# HandHeld_O2_Analyzer.net
KiCad netlist of a schematic drawn in EAGLE
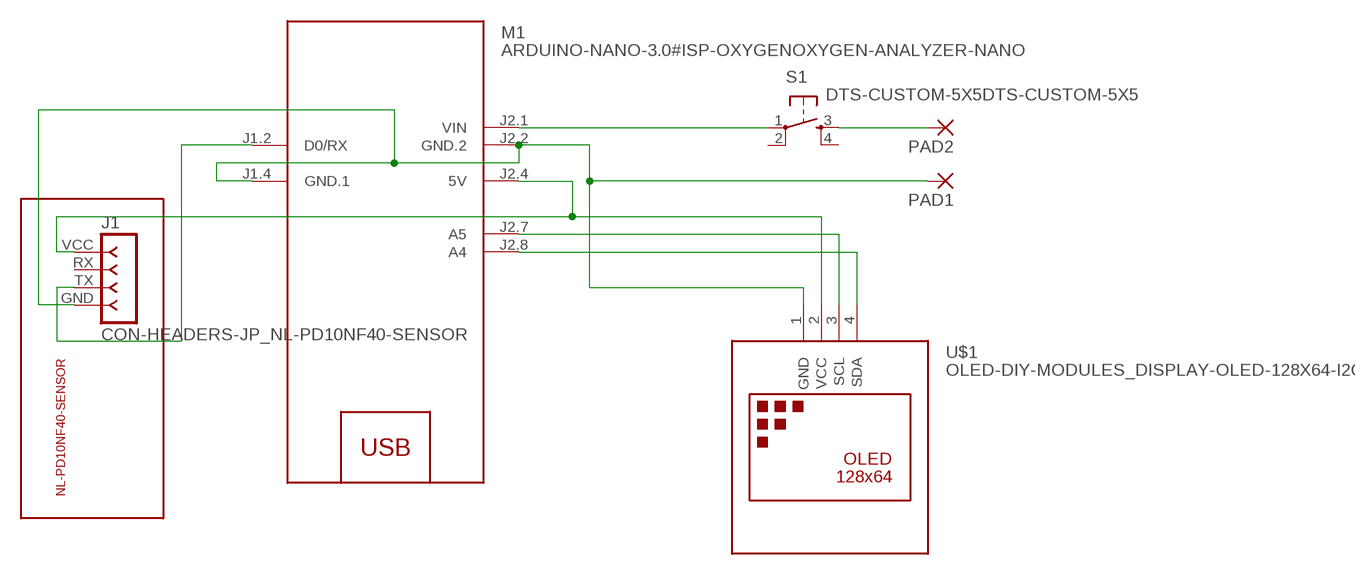
[diagram p0: schematic, sheet 1]

(export (version "E")
  (design (tool "Eeschema 10.0.6"))
  (components
    (comp (ref "J1")
      (value "CON-HEADERS-JP_NL-PD10NF40-SENSOR")
      (footprint "eagle-import:CON-HEADERS-JP_NL-PD10NF40-SENSOR")
      (libsource (lib "eagle-import") (part "CON-HEADERS-JP_NL-PD10NF40-SENSOR"))
    )
    (comp (ref "M1")
      (value "ARDUINO-NANO-3.0#ISP-OXYGENOXYGEN-ANALYZER-NANO")
      (footprint "eagle-import:ARDUINO-NANO-3.0#ISP-OXYGEN")
      (libsource (lib "eagle-import") (part "ARDUINO-NANO-3.0#ISP-OXYGENOXYGEN-ANALYZER-NANO"))
    )
    (comp (ref "PAD1")
      (value "WIREPAD_2,54/0,8")
      (footprint "eagle-import:WIREPAD_2,54_0,8")
      (libsource (lib "eagle-import") (part "WIREPAD_2,54/0,8"))
    )
    (comp (ref "PAD2")
      (value "WIREPAD_2,54/0,8")
      (footprint "eagle-import:WIREPAD_2,54_0,8")
      (libsource (lib "eagle-import") (part "WIREPAD_2,54/0,8"))
    )
    (comp (ref "S1")
      (value "DTS-CUSTOM-5X5DTS-CUSTOM-5X5")
      (footprint "eagle-import:DTS-CUSTOM-5X5")
      (libsource (lib "eagle-import") (part "DTS-CUSTOM-5X5DTS-CUSTOM-5X5"))
    )
    (comp (ref "U$1")
      (value "OLED-DIY-MODULES_DISPLAY-OLED-128X64-I2C")
      (footprint "eagle-import:OLED-DIY-MODULES_DISPLAY-OLED-128X64-I2C")
      (libsource (lib "eagle-import") (part "OLED-DIY-MODULES_DISPLAY-OLED-128X64-I2C"))
    )
  )
  (nets
    (net (code "1") (name "Net-(M1-5V)") (class "Default")
      (node (ref "J1") (pin "VCC") (pinfunction "VCC_VCC") (pintype "passive"))
      (node (ref "M1") (pin "J2.4") (pinfunction "5V_J2.4") (pintype "power_in"))
      (node (ref "U$1") (pin "2") (pinfunction "VCC_2") (pintype "power_in"))
    )
    (net (code "2") (name "Net-(M1-A4)") (class "Default")
      (node (ref "M1") (pin "J2.8") (pinfunction "A4_J2.8") (pintype "bidirectional"))
      (node (ref "U$1") (pin "4") (pinfunction "SDA_4") (pintype "bidirectional"))
    )
    (net (code "3") (name "Net-(M1-A5)") (class "Default")
      (node (ref "M1") (pin "J2.7") (pinfunction "A5_J2.7") (pintype "bidirectional"))
      (node (ref "U$1") (pin "3") (pinfunction "SCL_3") (pintype "bidirectional"))
    )
    (net (code "4") (name "Net-(M1-D0{slash}RX)") (class "Default")
      (node (ref "J1") (pin "TX") (pinfunction "TX_TX") (pintype "passive"))
      (node (ref "M1") (pin "J1.2") (pinfunction "D0/RX_J1.2") (pintype "bidirectional"))
    )
    (net (code "5") (name "Net-(M1-GND.1)") (class "Default")
      (node (ref "J1") (pin "GND") (pinfunction "GND_GND") (pintype "passive"))
      (node (ref "M1") (pin "J1.4") (pinfunction "GND.1_J1.4") (pintype "power_in"))
      (node (ref "M1") (pin "J2.2") (pinfunction "GND.2_J2.2") (pintype "power_in"))
      (node (ref "PAD1") (pin "1") (pinfunction "P_1") (pintype "passive"))
      (node (ref "U$1") (pin "1") (pinfunction "GND_1") (pintype "power_in"))
    )
    (net (code "6") (name "Net-(M1-VIN)") (class "Default")
      (node (ref "M1") (pin "J2.1") (pinfunction "VIN_J2.1") (pintype "power_in"))
      (node (ref "S1") (pin "1") (pinfunction "1_1") (pintype "passive"))
    )
    (net (code "7") (name "Net-(PAD2-P)") (class "Default")
      (node (ref "PAD2") (pin "1") (pinfunction "P_1") (pintype "passive"))
      (node (ref "S1") (pin "3") (pinfunction "3_3") (pintype "passive"))
    )
    (net (code "8") (name "unconnected-(J1-PadRX)") (class "Default")
      (node (ref "J1") (pin "RX") (pinfunction "RX_RX") (pintype "passive"))
    )
    (net (code "9") (name "unconnected-(S1-Pad2)") (class "Default")
      (node (ref "S1") (pin "2") (pinfunction "2_2") (pintype "passive"))
    )
    (net (code "10") (name "unconnected-(S1-Pad4)") (class "Default")
      (node (ref "S1") (pin "4") (pinfunction "4_4") (pintype "passive"))
    )
  )
)
